# DVT-Levelshifert-HT.net
KiCad netlist of a schematic drawn in Altium Designer
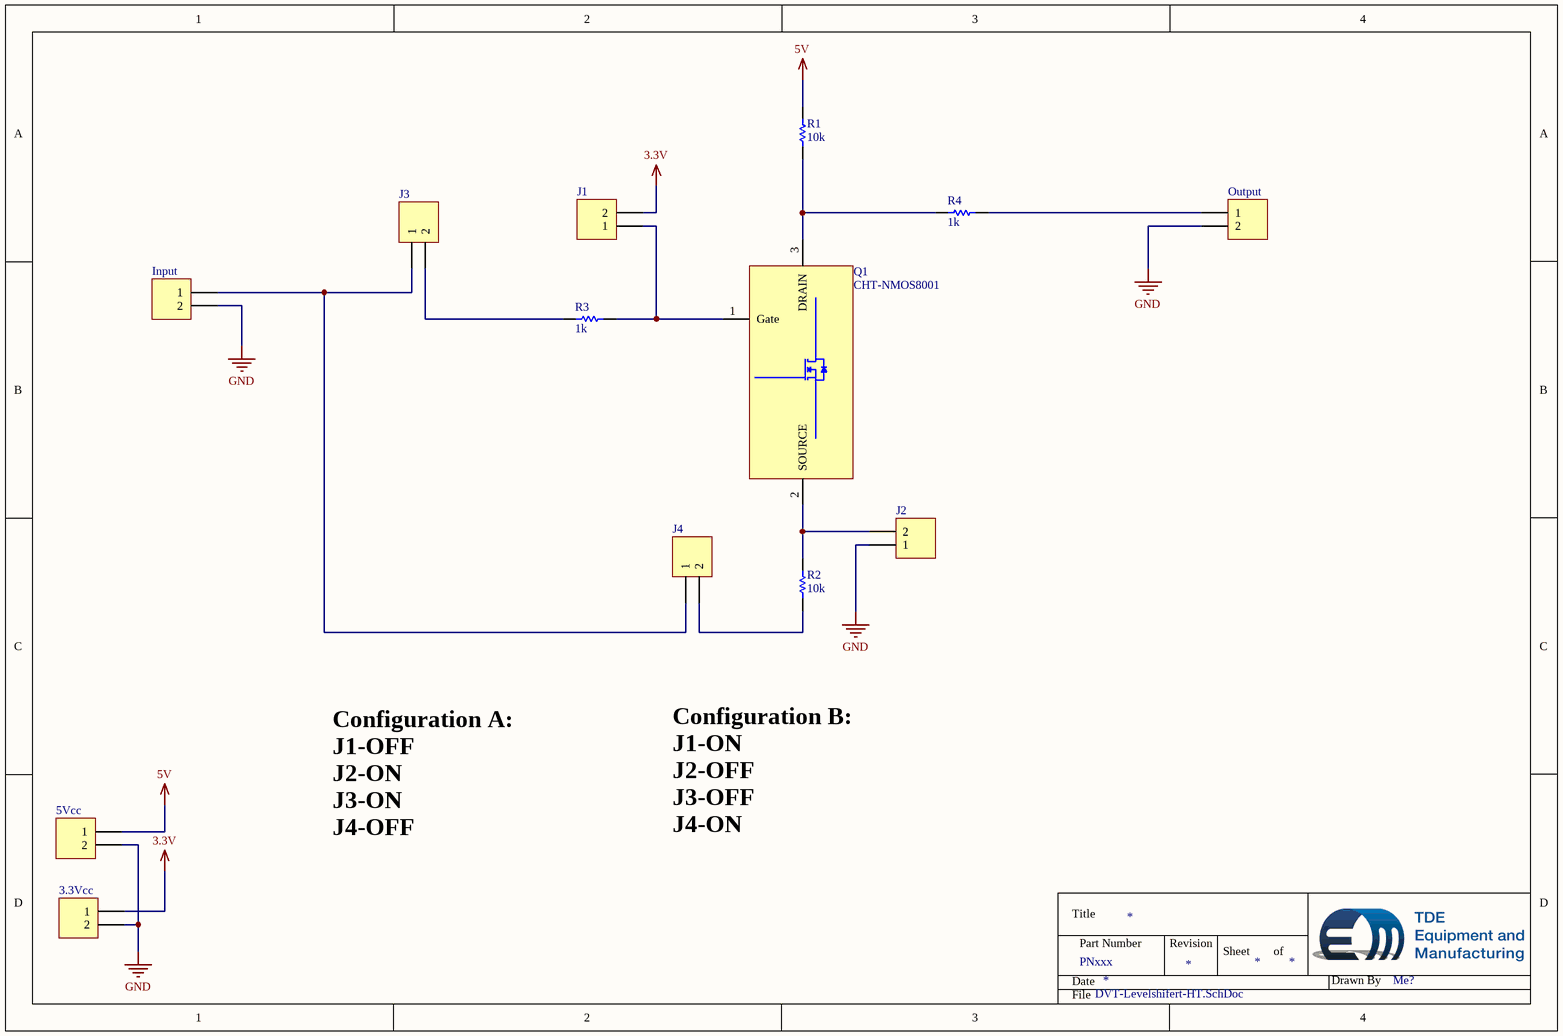
[diagram p0: DVT-Levelshifert-HT.SchDoc]

(export (version "E")
  (design (tool "Eeschema 10.0.6"))
  (components
    (comp (ref "3.3Vcc")
      (value "PHOENIX_1715721")
      (footprint "Phoenix-2-5_08")
      (description "Phoenix, 2 pol, 5.08mm, 22A, 715721")
      (fields (field (name "MANUFACTURER") "Phoenix") (field (name "PUBLISHER") "Sebastian Kulik"))
      (libsource (lib "Connectors") (part "2Pol_1715721"))
    )
    (comp (ref "5Vcc")
      (value "PHOENIX_1715721")
      (footprint "Phoenix-2-5_08")
      (description "Phoenix, 2 pol, 5.08mm, 22A, 715721")
      (fields (field (name "MANUFACTURER") "Phoenix") (field (name "PUBLISHER") "Sebastian Kulik"))
      (libsource (lib "Connectors") (part "2Pol_1715721"))
    )
    (comp (ref "Input")
      (value "PHOENIX_1715721")
      (footprint "Phoenix-2-5_08")
      (description "Phoenix, 2 pol, 5.08mm, 22A, 715721")
      (fields (field (name "MANUFACTURER") "Phoenix") (field (name "PUBLISHER") "Sebastian Kulik"))
      (libsource (lib "Connectors") (part "2Pol_1715721"))
    )
    (comp (ref "J1")
      (value "PHOENIX_1715721")
      (footprint "HDR1X2")
      (description "Plug, 2-Pin")
      (fields (field (name "MANUFACTURER") "WE") (field (name "PUBLISHER") "Sebastian Kulik"))
      (libsource (lib "Connectors") (part "Plug_2_90_2.54"))
    )
    (comp (ref "J2")
      (value "PHOENIX_1715721")
      (footprint "HDR1X2")
      (description "Plug, 2-Pin")
      (fields (field (name "MANUFACTURER") "WE") (field (name "PUBLISHER") "Sebastian Kulik"))
      (libsource (lib "") (part "Plug_2_90_2.54_1"))
    )
    (comp (ref "J3")
      (value "PHOENIX_1715721")
      (footprint "HDR1X2")
      (description "Plug, 2-Pin")
      (fields (field (name "MANUFACTURER") "WE") (field (name "PUBLISHER") "Sebastian Kulik"))
      (libsource (lib "") (part "Plug_2_90_2.54_1"))
    )
    (comp (ref "J4")
      (value "PHOENIX_1715721")
      (footprint "HDR1X2")
      (description "Plug, 2-Pin")
      (fields (field (name "MANUFACTURER") "WE") (field (name "PUBLISHER") "Sebastian Kulik"))
      (libsource (lib "") (part "Plug_2_90_2.54_1"))
    )
    (comp (ref "Output")
      (value "PHOENIX_1715721")
      (footprint "Phoenix-2-5_08")
      (description "Phoenix, 2 pol, 5.08mm, 22A, 715721")
      (fields (field (name "MANUFACTURER") "Phoenix") (field (name "PUBLISHER") "Sebastian Kulik"))
      (libsource (lib "") (part "2Pol_1715721_1"))
    )
    (comp (ref "Q1")
      (value "CHT-NMOS8001")
      (footprint "TDFP16 - NMOS8001")
      (description "Comparator, Hi-Temp, 25MHz")
      (fields (field (name "MANUFACTURER") "CISSOID") (field (name "PUBLISHER") "Sebastian Kulik"))
      (libsource (lib "Discrete") (part "CHT-NMOS8001"))
    )
    (comp (ref "R1")
      (value "10k")
      (footprint "Dummy-10mm")
      (description "Resistor-Dummy-THT")
      (fields (field (name "PUBLISHER") "Sebastian Kulik"))
      (libsource (lib "Resistors") (part "Resistor-Dummy-THT"))
    )
    (comp (ref "R2")
      (value "10k")
      (footprint "Dummy-10mm")
      (description "Resistor-Dummy-THT")
      (fields (field (name "PUBLISHER") "Sebastian Kulik"))
      (libsource (lib "Resistors") (part "Resistor-Dummy-THT"))
    )
    (comp (ref "R3")
      (value "1k")
      (footprint "Dummy-10mm")
      (description "Resistor-Dummy-THT")
      (fields (field (name "PUBLISHER") "Sebastian Kulik"))
      (libsource (lib "Resistors") (part "Resistor-Dummy-THT"))
    )
    (comp (ref "R4")
      (value "1k")
      (footprint "Dummy-10mm")
      (description "Resistor-Dummy-THT")
      (fields (field (name "PUBLISHER") "Sebastian Kulik"))
      (libsource (lib "Resistors") (part "Resistor-Dummy-THT"))
    )
  )
  (nets
    (net (code "1") (name "3.3V") (class "Default")
      (node (ref "3.3Vcc") (pin "1") (pinfunction "1_1") (pintype "passive"))
      (node (ref "J1") (pin "2") (pinfunction "2_2") (pintype "passive"))
    )
    (net (code "2") (name "5V") (class "Default")
      (node (ref "5Vcc") (pin "1") (pinfunction "1_1") (pintype "passive"))
      (node (ref "R1") (pin "2") (pinfunction "2_2") (pintype "passive"))
    )
    (net (code "3") (name "GND") (class "Default")
      (node (ref "3.3Vcc") (pin "2") (pinfunction "2_2") (pintype "passive"))
      (node (ref "5Vcc") (pin "2") (pinfunction "2_2") (pintype "passive"))
      (node (ref "Input") (pin "2") (pinfunction "2_2") (pintype "passive"))
      (node (ref "J2") (pin "1") (pinfunction "1_1") (pintype "passive"))
      (node (ref "Output") (pin "2") (pinfunction "2_2") (pintype "passive"))
    )
    (net (code "4") (name "Net-(Input-Pad1)") (class "Default")
      (node (ref "Input") (pin "1") (pinfunction "1_1") (pintype "passive"))
      (node (ref "J3") (pin "1") (pinfunction "1_1") (pintype "passive"))
      (node (ref "J4") (pin "1") (pinfunction "1_1") (pintype "passive"))
    )
    (net (code "5") (name "Net-(J3-Pad2)") (class "Default")
      (node (ref "J3") (pin "2") (pinfunction "2_2") (pintype "passive"))
      (node (ref "R3") (pin "2") (pinfunction "2_2") (pintype "passive"))
    )
    (net (code "6") (name "Net-(J4-Pad2)") (class "Default")
      (node (ref "J4") (pin "2") (pinfunction "2_2") (pintype "passive"))
      (node (ref "R2") (pin "1") (pinfunction "1_1") (pintype "passive"))
    )
    (net (code "7") (name "Net-(Output-Pad1)") (class "Default")
      (node (ref "Output") (pin "1") (pinfunction "1_1") (pintype "passive"))
      (node (ref "R4") (pin "1") (pinfunction "1_1") (pintype "passive"))
    )
    (net (code "8") (name "Net-(Q1-DRAIN)") (class "Default")
      (node (ref "Q1") (pin "3") (pinfunction "DRAIN_3") (pintype "power_in"))
      (node (ref "R1") (pin "1") (pinfunction "1_1") (pintype "passive"))
      (node (ref "R4") (pin "2") (pinfunction "2_2") (pintype "passive"))
    )
    (net (code "9") (name "Net-(Q1-Gate)") (class "Default")
      (node (ref "J1") (pin "1") (pinfunction "1_1") (pintype "passive"))
      (node (ref "Q1") (pin "1") (pinfunction "Gate_1") (pintype "passive"))
      (node (ref "R3") (pin "1") (pinfunction "1_1") (pintype "passive"))
    )
    (net (code "10") (name "Net-(Q1-SOURCE)") (class "Default")
      (node (ref "J2") (pin "2") (pinfunction "2_2") (pintype "passive"))
      (node (ref "Q1") (pin "2") (pinfunction "SOURCE_2") (pintype "passive"))
      (node (ref "R2") (pin "2") (pinfunction "2_2") (pintype "passive"))
    )
  )
)
